# AnalogSwitch.net
KiCad netlist of a schematic drawn in Altium Designer
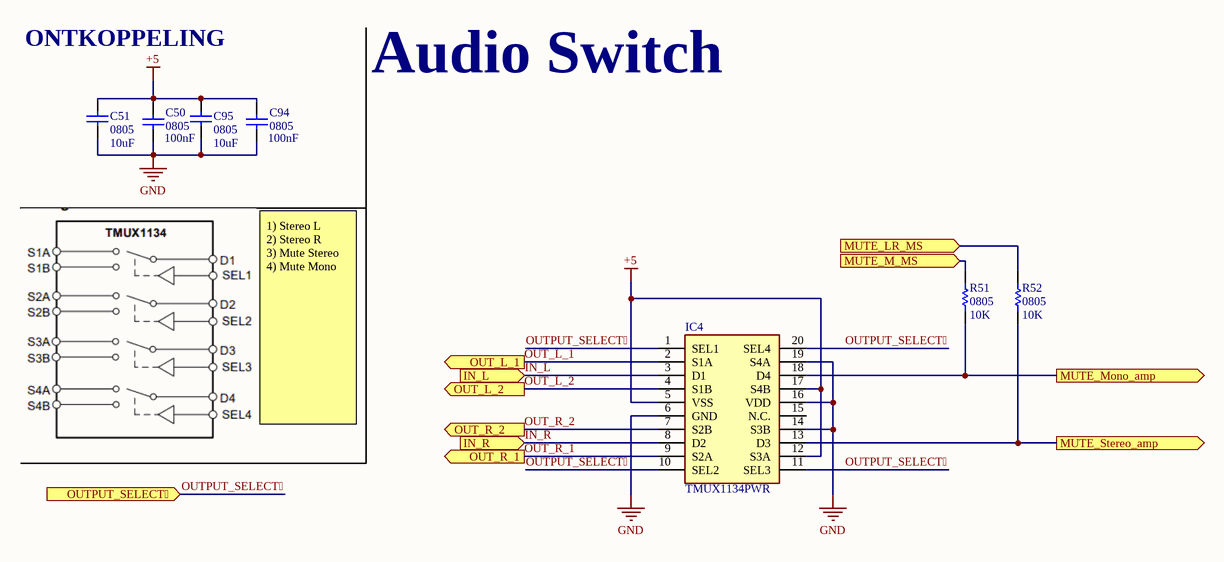
[diagram p0: AnalogSwitch.SchDoc]

(export (version "E")
  (design (tool "Eeschema 10.0.6"))
  (components
    (comp (ref "C50")
      (value "0805")
      (footprint "6-0805_N")
      (description "Capacitor")
      (fields (field (name "ALTIUM_VALUE") "100nF") (field (name "PUBLISHER") "Altium Limited"))
      (libsource (lib "Miscellaneous Devices") (part "Cap"))
    )
    (comp (ref "C51")
      (value "0805")
      (footprint "6-0805_N")
      (description "Capacitor")
      (fields (field (name "ALTIUM_VALUE") "10uF") (field (name "PUBLISHER") "Altium Limited"))
      (libsource (lib "Miscellaneous Devices") (part "Cap"))
    )
    (comp (ref "C94")
      (value "0805")
      (footprint "6-0805_N")
      (description "Capacitor")
      (fields (field (name "ALTIUM_VALUE") "100nF") (field (name "PUBLISHER") "Altium Limited"))
      (libsource (lib "Miscellaneous Devices") (part "Cap"))
    )
    (comp (ref "C95")
      (value "0805")
      (footprint "6-0805_N")
      (description "Capacitor")
      (fields (field (name "ALTIUM_VALUE") "10uF") (field (name "PUBLISHER") "Altium Limited"))
      (libsource (lib "Miscellaneous Devices") (part "Cap"))
    )
    (comp (ref "IC4")
      (value "TMUX1134PWR")
      (footprint "SamacSys:SOP65P640X120-20N")
      (description "Integrated Circuit")
      (fields (field (name "MOUSER PART NUMBER") "595-TMUX1134PWR"))
      (libsource (lib "*") (part "TMUX1134PWR"))
    )
    (comp (ref "R51")
      (value "0805")
      (footprint "6-0805_N")
      (description "Resistor")
      (fields (field (name "ALTIUM_VALUE") "10K") (field (name "PUBLISHER") "Altium Limited"))
      (libsource (lib "Miscellaneous Devices") (part "Res1"))
    )
    (comp (ref "R52")
      (value "0805")
      (footprint "6-0805_N")
      (description "Resistor")
      (fields (field (name "ALTIUM_VALUE") "10K") (field (name "PUBLISHER") "Altium Limited"))
      (libsource (lib "Miscellaneous Devices") (part "Res1"))
    )
  )
  (nets
    (net (code "1") (name "+5") (class "Default")
      (node (ref "C50") (pin "1") (pinfunction "1_1") (pintype "passive"))
      (node (ref "C51") (pin "1") (pinfunction "1_1") (pintype "passive"))
      (node (ref "C94") (pin "1") (pinfunction "1_1") (pintype "passive"))
      (node (ref "C95") (pin "1") (pinfunction "1_1") (pintype "passive"))
      (node (ref "IC4") (pin "12") (pinfunction "S3A_12") (pintype "passive"))
      (node (ref "IC4") (pin "17") (pinfunction "S4B_17") (pintype "passive"))
      (node (ref "IC4") (pin "5") (pinfunction "VSS_5") (pintype "passive"))
    )
    (net (code "2") (name "/IN_L") (class "Default")
      (node (ref "IC4") (pin "3") (pinfunction "D1_3") (pintype "passive"))
    )
    (net (code "3") (name "/IN_R") (class "Default")
      (node (ref "IC4") (pin "8") (pinfunction "D2_8") (pintype "passive"))
    )
    (net (code "4") (name "/MUTE_LR_MS") (class "Default")
      (node (ref "R52") (pin "2") (pinfunction "2_2") (pintype "passive"))
    )
    (net (code "5") (name "/MUTE_M_MS") (class "Default")
      (node (ref "R51") (pin "2") (pinfunction "2_2") (pintype "passive"))
    )
    (net (code "6") (name "/MUTE_Mono_amp") (class "Default")
      (node (ref "IC4") (pin "18") (pinfunction "D4_18") (pintype "passive"))
      (node (ref "R51") (pin "1") (pinfunction "1_1") (pintype "passive"))
    )
    (net (code "7") (name "/MUTE_Stereo_amp") (class "Default")
      (node (ref "IC4") (pin "13") (pinfunction "D3_13") (pintype "passive"))
      (node (ref "R52") (pin "1") (pinfunction "1_1") (pintype "passive"))
    )
    (net (code "8") (name "/OUTPUT_SELECT") (class "Default")
      (node (ref "IC4") (pin "1") (pinfunction "SEL1_1") (pintype "passive"))
      (node (ref "IC4") (pin "10") (pinfunction "SEL2_10") (pintype "passive"))
      (node (ref "IC4") (pin "11") (pinfunction "SEL3_11") (pintype "passive"))
      (node (ref "IC4") (pin "20") (pinfunction "SEL4_20") (pintype "passive"))
    )
    (net (code "9") (name "/OUT_L_1") (class "Default")
      (node (ref "IC4") (pin "2") (pinfunction "S1A_2") (pintype "passive"))
    )
    (net (code "10") (name "/OUT_L_2") (class "Default")
      (node (ref "IC4") (pin "4") (pinfunction "S1B_4") (pintype "passive"))
    )
    (net (code "11") (name "/OUT_R_1") (class "Default")
      (node (ref "IC4") (pin "9") (pinfunction "S2A_9") (pintype "passive"))
    )
    (net (code "12") (name "/OUT_R_2") (class "Default")
      (node (ref "IC4") (pin "7") (pinfunction "S2B_7") (pintype "passive"))
    )
    (net (code "13") (name "GND") (class "Default")
      (node (ref "C50") (pin "2") (pinfunction "2_2") (pintype "passive"))
      (node (ref "C51") (pin "2") (pinfunction "2_2") (pintype "passive"))
      (node (ref "C94") (pin "2") (pinfunction "2_2") (pintype "passive"))
      (node (ref "C95") (pin "2") (pinfunction "2_2") (pintype "passive"))
      (node (ref "IC4") (pin "14") (pinfunction "S3B_14") (pintype "passive"))
      (node (ref "IC4") (pin "16") (pinfunction "VDD_16") (pintype "passive"))
      (node (ref "IC4") (pin "19") (pinfunction "S4A_19") (pintype "passive"))
      (node (ref "IC4") (pin "6") (pinfunction "GND_6") (pintype "passive"))
    )
    (net (code "14") (name "unconnected-(IC4-N.C.-Pad15)") (class "Default")
      (node (ref "IC4") (pin "15") (pinfunction "N.C._15") (pintype "passive"))
    )
  )
)
